# 1__schdoc.net
KiCad netlist of a schematic drawn in Altium Designer
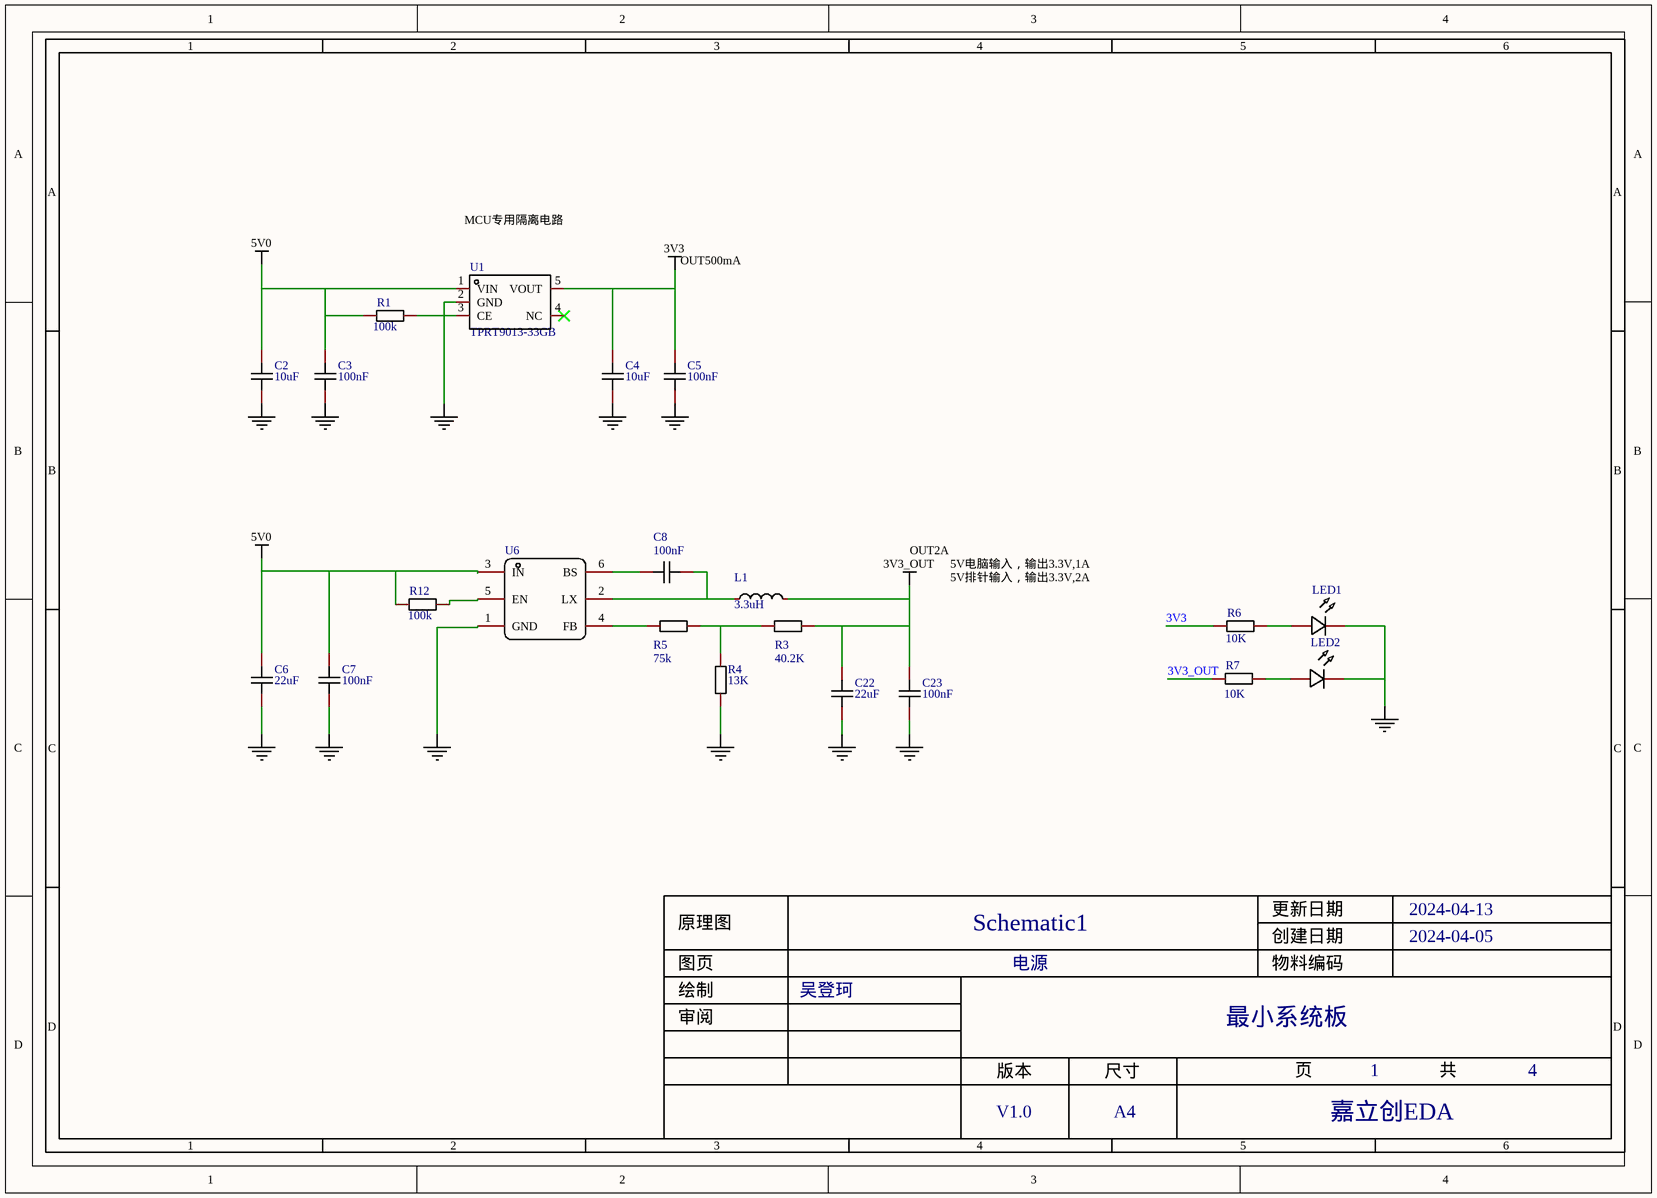
[diagram p0: 1_电源.schdoc.schdoc]

(export (version "E")
  (design (tool "Eeschema 10.0.6"))
  (components
    (comp (ref "C2")
      (value "10uF")
      (fields (field (name "NAME") "10uF"))
      (libsource (lib "altium-import") (part "root_1_CAP_0603_"))
    )
    (comp (ref "C3")
      (value "100nF")
      (fields (field (name "NAME") "100nF"))
      (libsource (lib "altium-import") (part "root_1_CAP_0603_"))
    )
    (comp (ref "C4")
      (value "10uF")
      (fields (field (name "NAME") "10uF"))
      (libsource (lib "altium-import") (part "root_1_CAP_0603_"))
    )
    (comp (ref "C5")
      (value "100nF")
      (fields (field (name "NAME") "100nF"))
      (libsource (lib "altium-import") (part "root_1_CAP_0603_"))
    )
    (comp (ref "C6")
      (value "22uF")
      (fields (field (name "NAME") "22uF"))
      (libsource (lib "altium-import") (part "root_1_CAP_1206_"))
    )
    (comp (ref "C7")
      (value "100nF")
      (fields (field (name "NAME") "100nF"))
      (libsource (lib "altium-import") (part "root_1_CAP_0603_"))
    )
    (comp (ref "C8")
      (value "100nF")
      (fields (field (name "NAME") "100nF"))
      (libsource (lib "altium-import") (part "root_0_CAP_0603_"))
    )
    (comp (ref "C22")
      (value "22uF")
      (fields (field (name "NAME") "22uF"))
      (libsource (lib "altium-import") (part "root_1_CAP_1206_"))
    )
    (comp (ref "C23")
      (value "100nF")
      (fields (field (name "NAME") "100nF"))
      (libsource (lib "altium-import") (part "root_1_CAP_0603_"))
    )
    (comp (ref "L1")
      (value "3.3uH")
      (fields
        (field (name "NAME") "3.3uH")
        (field (name "MANUFACTURER") "PSA(信昌电陶)")
        (field (name "MANUFACTURER PART") "MCS0630-2R2MPY1")
        (field (name "TOLERANCE") "±20%")
      )
      (libsource (lib "altium-import") (part "root_0_MCS0630-2R2MPY1_"))
    )
    (comp (ref "LED1") (value "LED_0603-R") (libsource (lib "altium-import") (part "root_0_LED_0603-R_")))
    (comp (ref "LED2") (value "LED_0603-R") (libsource (lib "altium-import") (part "root_0_LED_0603-R_")))
    (comp (ref "R1")
      (value "100k")
      (fields (field (name "NAME") "100k"))
      (libsource (lib "altium-import") (part "root_0_Res_0603_"))
    )
    (comp (ref "R3")
      (value "40.2K")
      (fields (field (name "NAME") "40.2K"))
      (libsource (lib "altium-import") (part "root_2_Res_0603_"))
    )
    (comp (ref "R4")
      (value "13K")
      (fields (field (name "NAME") "13K"))
      (libsource (lib "altium-import") (part "root_1_Res_0603_"))
    )
    (comp (ref "R5")
      (value "75k")
      (fields (field (name "NAME") "75k"))
      (libsource (lib "altium-import") (part "root_0_Res_0603_"))
    )
    (comp (ref "R6")
      (value "10K")
      (fields (field (name "NAME") "10K"))
      (libsource (lib "altium-import") (part "root_0_Res_0603_"))
    )
    (comp (ref "R7")
      (value "10K")
      (fields (field (name "NAME") "10K"))
      (libsource (lib "altium-import") (part "root_0_Res_0603_"))
    )
    (comp (ref "R12")
      (value "100k")
      (fields (field (name "NAME") "100k"))
      (libsource (lib "altium-import") (part "root_0_Res_0603_"))
    )
    (comp (ref "U1")
      (value "TPRT9013-33GB")
      (description "输出类型:-;")
      (fields (field (name "NAME") "TPRT9013-33GB") (field (name "MANUFACTURER") "TECH PUBLIC(台舟)"))
      (libsource (lib "altium-import") (part "root_0_TPRT9013-33GB_"))
    )
    (comp (ref "U6")
      (value "TPMP1470GJ-Z")
      (fields (field (name "MANUFACTURER") "TECH PUBLIC(台舟)"))
      (libsource (lib "altium-import") (part "root_0_TPMP1470GJ-Z_"))
    )
  )
  (nets
    (net (code "1") (name "3V3") (class "Default")
      (node (ref "C4") (pin "2") (pinfunction "2_2") (pintype "passive"))
      (node (ref "C5") (pin "2") (pinfunction "2_2") (pintype "passive"))
      (node (ref "R6") (pin "1") (pinfunction "1_1") (pintype "passive"))
      (node (ref "U1") (pin "5") (pinfunction "VOUT_5") (pintype "passive"))
    )
    (net (code "2") (name "3V3_OUT") (class "Default")
      (node (ref "C22") (pin "2") (pinfunction "2_2") (pintype "passive"))
      (node (ref "C23") (pin "2") (pinfunction "2_2") (pintype "passive"))
      (node (ref "L1") (pin "2") (pinfunction "2_2") (pintype "passive"))
      (node (ref "R3") (pin "1") (pinfunction "1_1") (pintype "passive"))
      (node (ref "R7") (pin "1") (pinfunction "1_1") (pintype "passive"))
    )
    (net (code "3") (name "5V0") (class "Default")
      (node (ref "C2") (pin "2") (pinfunction "2_2") (pintype "passive"))
      (node (ref "C3") (pin "2") (pinfunction "2_2") (pintype "passive"))
      (node (ref "C6") (pin "2") (pinfunction "2_2") (pintype "passive"))
      (node (ref "C7") (pin "2") (pinfunction "2_2") (pintype "passive"))
      (node (ref "R1") (pin "1") (pinfunction "1_1") (pintype "passive"))
      (node (ref "R12") (pin "1") (pinfunction "1_1") (pintype "passive"))
      (node (ref "U1") (pin "1") (pinfunction "VIN_1") (pintype "passive"))
      (node (ref "U6") (pin "3") (pinfunction "IN_3") (pintype "passive"))
    )
    (net (code "4") (name "<NO NET>") (class "Default")
      (node (ref "C2") (pin "1") (pinfunction "1_1") (pintype "passive"))
      (node (ref "C22") (pin "1") (pinfunction "1_1") (pintype "passive"))
      (node (ref "C23") (pin "1") (pinfunction "1_1") (pintype "passive"))
      (node (ref "C3") (pin "1") (pinfunction "1_1") (pintype "passive"))
      (node (ref "C4") (pin "1") (pinfunction "1_1") (pintype "passive"))
      (node (ref "C5") (pin "1") (pinfunction "1_1") (pintype "passive"))
      (node (ref "C6") (pin "1") (pinfunction "1_1") (pintype "passive"))
      (node (ref "C7") (pin "1") (pinfunction "1_1") (pintype "passive"))
      (node (ref "LED1") (pin "1") (pinfunction "C_1") (pintype "passive"))
      (node (ref "LED2") (pin "1") (pinfunction "C_1") (pintype "passive"))
      (node (ref "R4") (pin "1") (pinfunction "1_1") (pintype "passive"))
      (node (ref "U1") (pin "2") (pinfunction "GND_2") (pintype "passive"))
      (node (ref "U6") (pin "1") (pinfunction "GND_1") (pintype "passive"))
    )
    (net (code "5") (name "Net-(LED1-A)") (class "Default")
      (node (ref "LED1") (pin "2") (pinfunction "A_2") (pintype "passive"))
      (node (ref "R6") (pin "2") (pinfunction "2_2") (pintype "passive"))
    )
    (net (code "6") (name "Net-(LED2-A)") (class "Default")
      (node (ref "LED2") (pin "2") (pinfunction "A_2") (pintype "passive"))
      (node (ref "R7") (pin "2") (pinfunction "2_2") (pintype "passive"))
    )
    (net (code "7") (name "Net-(R3-Pad2)") (class "Default")
      (node (ref "R3") (pin "2") (pinfunction "2_2") (pintype "passive"))
      (node (ref "R4") (pin "2") (pinfunction "2_2") (pintype "passive"))
      (node (ref "R5") (pin "2") (pinfunction "2_2") (pintype "passive"))
    )
    (net (code "8") (name "Net-(U1-CE)") (class "Default")
      (node (ref "R1") (pin "2") (pinfunction "2_2") (pintype "passive"))
      (node (ref "U1") (pin "3") (pinfunction "CE_3") (pintype "passive"))
    )
    (net (code "9") (name "Net-(U6-BS)") (class "Default")
      (node (ref "C8") (pin "1") (pinfunction "1_1") (pintype "passive"))
      (node (ref "U6") (pin "6") (pinfunction "BS_6") (pintype "passive"))
    )
    (net (code "10") (name "Net-(U6-EN)") (class "Default")
      (node (ref "R12") (pin "2") (pinfunction "2_2") (pintype "passive"))
      (node (ref "U6") (pin "5") (pinfunction "EN_5") (pintype "passive"))
    )
    (net (code "11") (name "Net-(U6-FB)") (class "Default")
      (node (ref "R5") (pin "1") (pinfunction "1_1") (pintype "passive"))
      (node (ref "U6") (pin "4") (pinfunction "FB_4") (pintype "passive"))
    )
    (net (code "12") (name "Net-(U6-LX)") (class "Default")
      (node (ref "C8") (pin "2") (pinfunction "2_2") (pintype "passive"))
      (node (ref "L1") (pin "1") (pinfunction "1_1") (pintype "passive"))
      (node (ref "U6") (pin "2") (pinfunction "LX_2") (pintype "passive"))
    )
    (net (code "13") (name "unconnected-(U1-NC-Pad4)") (class "Default")
      (node (ref "U1") (pin "4") (pinfunction "NC_4") (pintype "passive+no_connect"))
    )
  )
)
